# STM32.net
KiCad netlist of a schematic drawn in Altium Designer
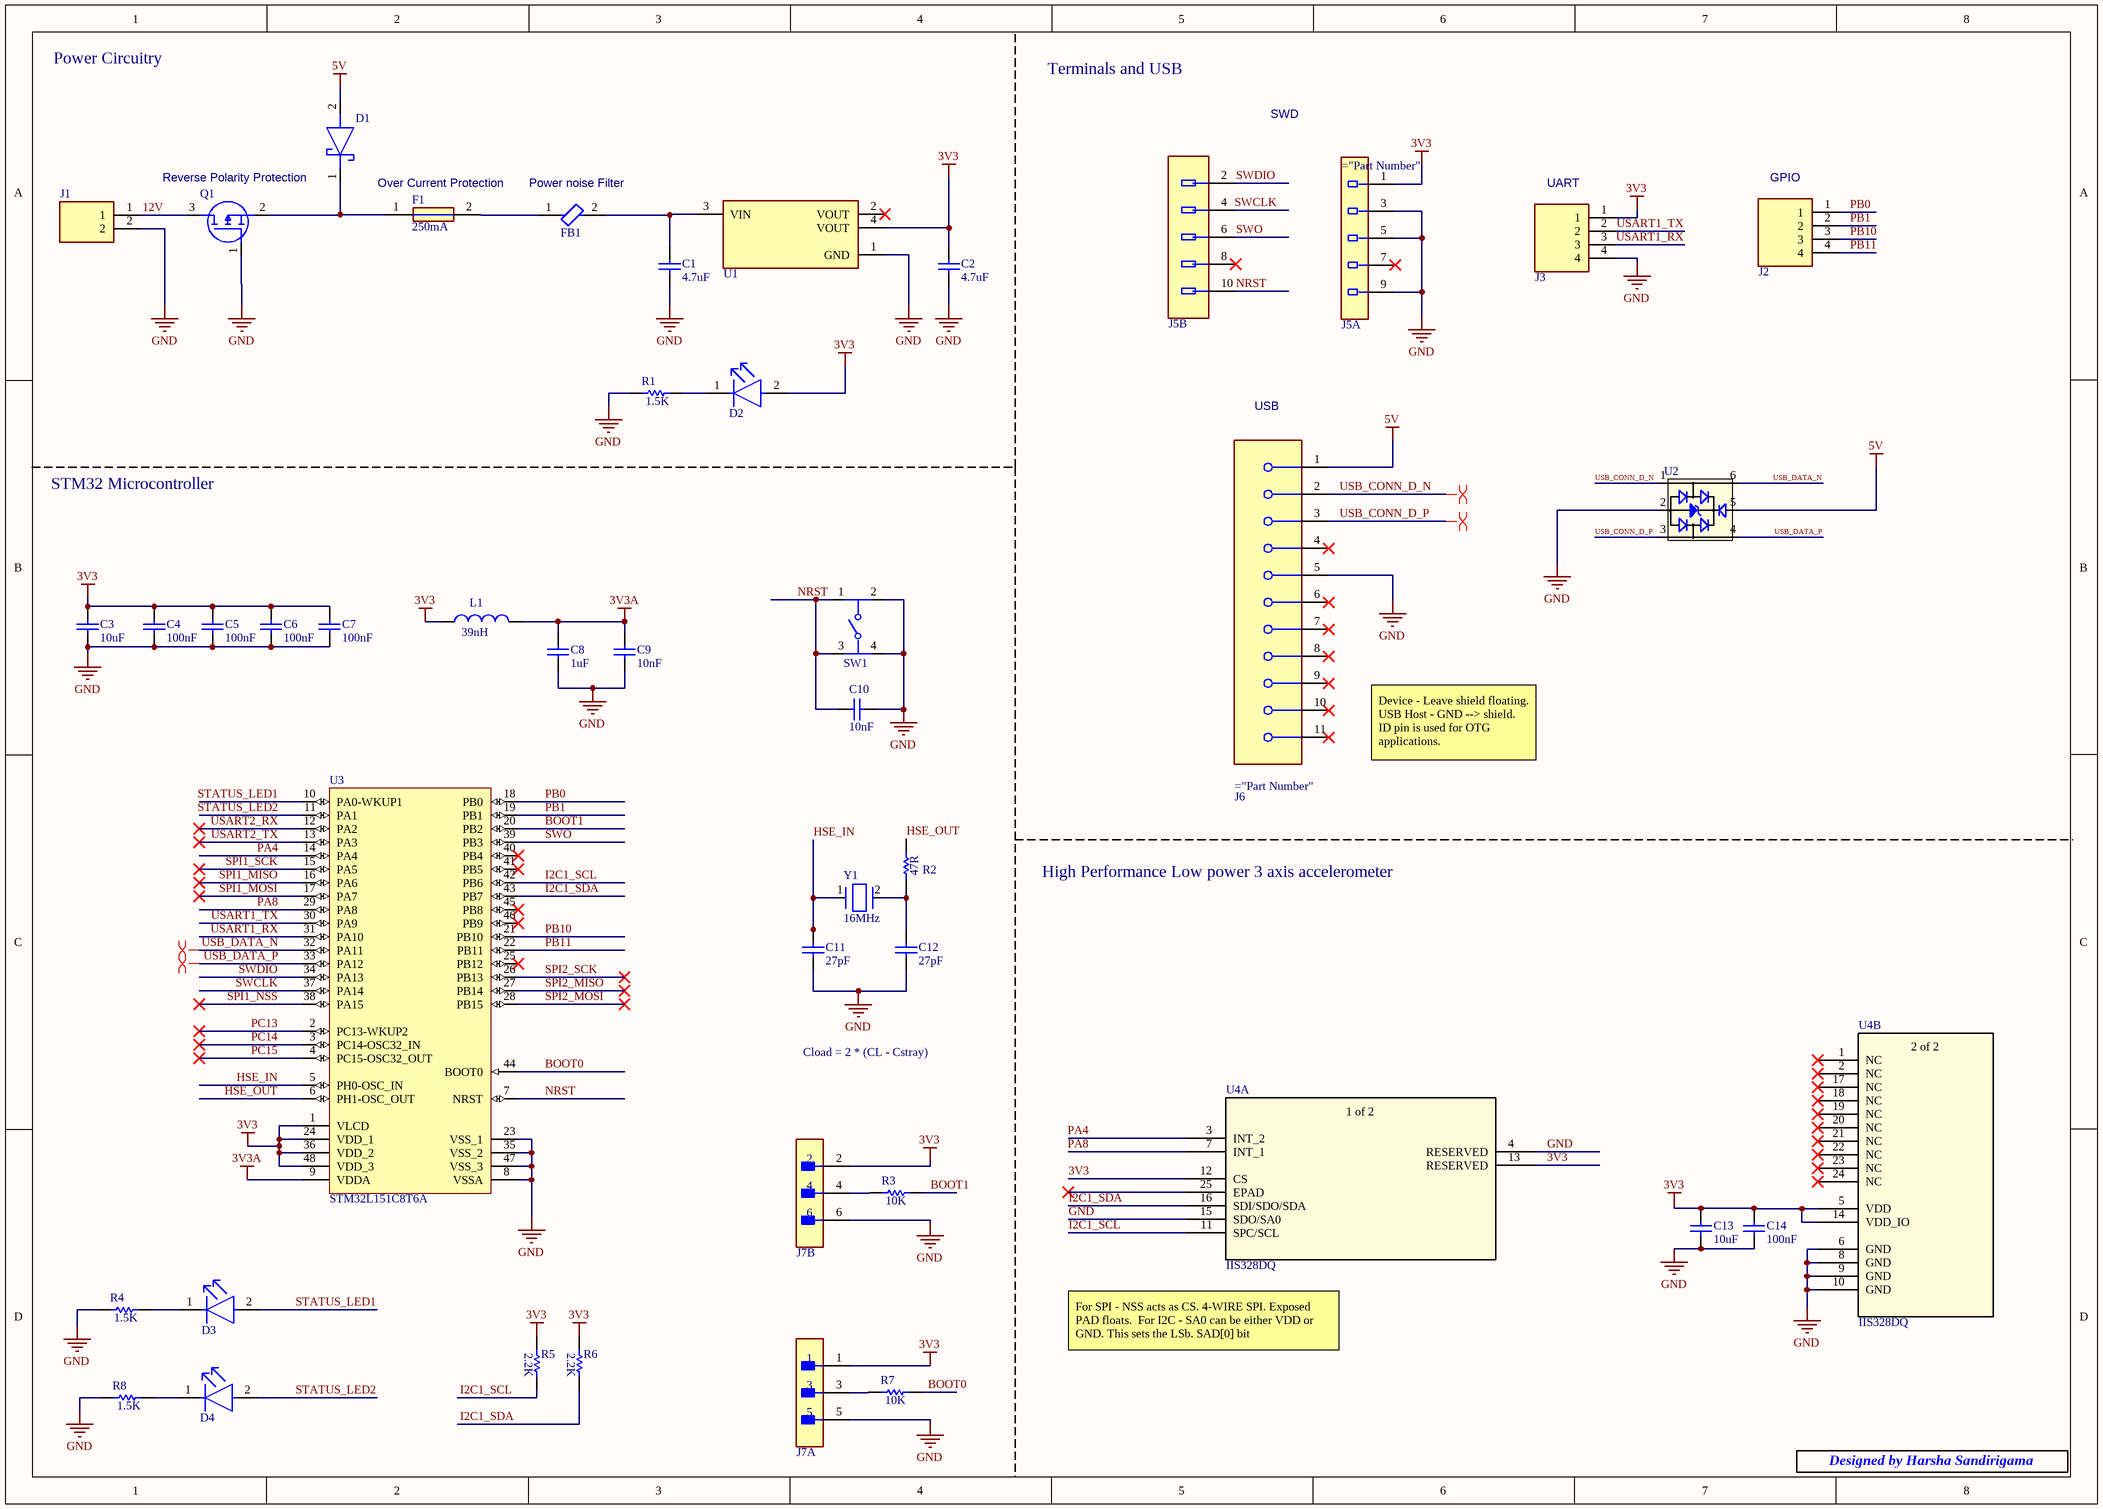
[diagram p0: STM32.SchDoc]

(export (version "E")
  (design (tool "Eeschema 10.0.6"))
  (components
    (comp (ref "C1")
      (value "4.7uF")
      (footprint "0603C - HD")
      (description "Cap Ceramic 4.7uF 10V X7S 10% SMD 0603 125°C Punched Paper T/R")
      (fields
        (field (name "MANUFACTURER") "TDK")
        (field (name "MANUFACTURER PART NUMBER") "C1608X7S1A475K080AC")
      )
      (libsource (lib "stm32devsch") (part "C1608X7S1A475K080AC"))
    )
    (comp (ref "C2")
      (value "4.7uF")
      (footprint "0603C - HD")
      (description "Cap Ceramic 4.7uF 10V X7S 10% SMD 0603 125°C Punched Paper T/R")
      (fields
        (field (name "MANUFACTURER") "TDK")
        (field (name "MANUFACTURER PART NUMBER") "C1608X7S1A475K080AC")
      )
      (libsource (lib "stm32devsch") (part "C1608X7S1A475K080AC"))
    )
    (comp (ref "C3")
      (value "10uF")
      (footprint "0603C - HD")
      (fields
        (field (name "MANUFACTURER") "Kyocera AVX")
        (field (name "MANUFACTURER PART NUMBER") "06036D106MAT2A")
        (field (name "TOLERANCE") "20%")
      )
      (libsource (lib "stm32devsch") (part "06036D106MAT2A"))
    )
    (comp (ref "C4")
      (value "100nF")
      (footprint "0603C - HD")
      (description "0.1 µF ±10% 50V Ceramic Capacitor X7R 0603 (1608 Metric)")
      (fields
        (field (name "MANUFACTURER") "Samsung")
        (field (name "MANUFACTURER PART NUMBER") "CL10B104KB8VPJC")
      )
      (libsource (lib "stm32devsch") (part "CL10B104KB8VPJC"))
    )
    (comp (ref "C5")
      (value "100nF")
      (footprint "0603C - HD")
      (description "0.1 µF ±10% 50V Ceramic Capacitor X7R 0603 (1608 Metric)")
      (fields
        (field (name "MANUFACTURER") "Samsung")
        (field (name "MANUFACTURER PART NUMBER") "CL10B104KB8VPJC")
      )
      (libsource (lib "stm32devsch") (part "CL10B104KB8VPJC"))
    )
    (comp (ref "C6")
      (value "100nF")
      (footprint "0603C - HD")
      (description "0.1 µF ±10% 50V Ceramic Capacitor X7R 0603 (1608 Metric)")
      (fields
        (field (name "MANUFACTURER") "Samsung")
        (field (name "MANUFACTURER PART NUMBER") "CL10B104KB8VPJC")
      )
      (libsource (lib "stm32devsch") (part "CL10B104KB8VPJC"))
    )
    (comp (ref "C7")
      (value "100nF")
      (footprint "0603C - HD")
      (description "0.1 µF ±10% 50V Ceramic Capacitor X7R 0603 (1608 Metric)")
      (fields
        (field (name "MANUFACTURER") "Samsung")
        (field (name "MANUFACTURER PART NUMBER") "CL10B104KB8VPJC")
      )
      (libsource (lib "stm32devsch") (part "CL10B104KB8VPJC"))
    )
    (comp (ref "C8")
      (value "1uF")
      (footprint "0603C - HD")
      (description "CAP CER 1UF 16V X7R 0603")
      (fields
        (field (name "MANUFACTURER") "Knowles Novacap")
        (field (name "MANUFACTURER PART NUMBER") "0603BB105K160YT")
      )
      (libsource (lib "stm32devsch") (part "0603BB105K160YT"))
    )
    (comp (ref "C9")
      (value "10nF")
      (footprint "0603C - HD")
      (description "Capacitor Ceramic 0.01uF 10% 50V 2-Pin Surface Mount T/R")
      (fields
        (field (name "MANUFACTURER") "Samsung")
        (field (name "MANUFACTURER PART NUMBER") "CL10B103KB8WPJC")
      )
      (libsource (lib "stm32devsch") (part "CL10B103KB8WPJC"))
    )
    (comp (ref "C10")
      (value "10nF")
      (footprint "0603C - HD")
      (description "Capacitor Ceramic 0.01uF 10% 50V 2-Pin Surface Mount T/R")
      (fields
        (field (name "MANUFACTURER") "Samsung")
        (field (name "MANUFACTURER PART NUMBER") "CL10B103KB8WPJC")
      )
      (libsource (lib "stm32devsch") (part "CL10B103KB8WPJC"))
    )
    (comp (ref "C11")
      (value "27pF")
      (footprint "0603C - HD")
      (description "CAP MLCC, 27PF, 50V, C0G/NP0, 5%, 0603")
      (fields
        (field (name "MANUFACTURER") "Kyocera AVX")
        (field (name "MANUFACTURER PART NUMBER") "06035A270JAT2A")
      )
      (libsource (lib "stm32devsch") (part "06035A270JAT2A"))
    )
    (comp (ref "C12")
      (value "27pF")
      (footprint "0603C - HD")
      (description "CAP MLCC, 27PF, 50V, C0G/NP0, 5%, 0603")
      (fields
        (field (name "MANUFACTURER") "Kyocera AVX")
        (field (name "MANUFACTURER PART NUMBER") "06035A270JAT2A")
      )
      (libsource (lib "stm32devsch") (part "06035A270JAT2A"))
    )
    (comp (ref "C13")
      (value "10uF")
      (footprint "0603C - HD")
      (fields
        (field (name "MANUFACTURER") "Kyocera AVX")
        (field (name "MANUFACTURER PART NUMBER") "06036D106MAT2A")
        (field (name "TOLERANCE") "20%")
      )
      (libsource (lib "stm32devsch") (part "06036D106MAT2A"))
    )
    (comp (ref "C14")
      (value "100nF")
      (footprint "0603C - HD")
      (description "0.1 µF ±10% 50V Ceramic Capacitor X7R 0603 (1608 Metric)")
      (fields
        (field (name "MANUFACTURER") "Samsung")
        (field (name "MANUFACTURER PART NUMBER") "CL10B104KB8VPJC")
      )
      (libsource (lib "stm32devsch") (part "CL10B104KB8VPJC"))
    )
    (comp (ref "D1")
      (value "PMEG4005CEJX")
      (footprint "SODFL2512X80N")
      (description "Rectifier Diode Schottky 40V 0.5A 1.8ns Automotive 2-Pin SOD-323F T/R")
      (fields (field (name "MOUSER PART NUMBER") "771-PMEG4005CEJX") (field (name "MANUFACTURER") "Nexperia"))
      (libsource (lib "stm32devsch") (part "PMEG4005CEJX"))
    )
    (comp (ref "D2")
      (value "LTST-C191KFKT")
      (footprint "Lite-On_0_MFG")
      (description "Orange 0603 130° Water Clear 90 mcd 2 V SMT Rectangular Flat Top LED")
      (fields (field (name "MANUFACTURER") "Vishay Lite-On"))
      (libsource (lib "stm32devsch") (part "LTST-C191KFKT"))
    )
    (comp (ref "D3")
      (value "LTST-C191KFKT")
      (footprint "Lite-On_0_MFG")
      (description "Orange 0603 130° Water Clear 90 mcd 2 V SMT Rectangular Flat Top LED")
      (fields (field (name "MANUFACTURER") "Vishay Lite-On"))
      (libsource (lib "stm32devsch") (part "LTST-C191KFKT"))
    )
    (comp (ref "D4")
      (value "LTST-C191KFKT")
      (footprint "Lite-On_0_MFG")
      (description "Orange 0603 130° Water Clear 90 mcd 2 V SMT Rectangular Flat Top LED")
      (fields (field (name "MANUFACTURER") "Vishay Lite-On"))
      (libsource (lib "stm32devsch") (part "LTST-C191KFKT"))
    )
    (comp (ref "F1")
      (value "250mA")
      (footprint "FUSC3115X66N")
      (description "Fuse Chip Very Fast Acting 0.25A 125V SMD Solder Pad 1206 Ceramic T/R CE/CSA/cULus")
      (fields (field (name "MANUFACTURER_PART_NUMBER") "C1Q250") (field (name "MANUFACTURER") "Bel"))
      (libsource (lib "stm32devsch") (part "C1Q250"))
    )
    (comp (ref "FB1")
      (value "MPZ1608Y101BTA00")
      (footprint "TDK_MPZ1608-0_8_IPC_A")
      (description "Ind Chip Bead Multi-Layer 100Ohm 25% 100MHz Ferrite 2A 0603 Punched Paper T/R")
      (fields (field (name "MANUFACTURER") "TDK") (field (name "TOLERANCE") "25%"))
      (libsource (lib "stm32devsch") (part "MPZ1608Y101BTA00"))
    )
    (comp (ref "J1")
      (value "12V")
      (footprint "PJ037AH")
      (description "CONN PWR JACK 2X5.5MM SOLDER")
      (fields
        (field (name "MANUFACTURER_PART_NUMBER") "PJ-037AH")
        (field (name "MOUSER PART NUMBER") "490-PJ-037AH")
      )
      (libsource (lib "stm32devsch") (part "PJ-037AH"))
    )
    (comp (ref "J2")
      (value "TS-104-T-AA")
      (footprint "HDRV4W46P0X254_1X4_1016X254X808P")
      (description "Connector")
      (fields (field (name "MOUSER PART NUMBER") "200-TS104TAA"))
      (libsource (lib "stm32devsch") (part "TS-104-T-AA"))
    )
    (comp (ref "J3")
      (value "TS-104-T-AA")
      (footprint "HDRV4W46P0X254_1X4_1016X254X808P")
      (description "Connector")
      (fields (field (name "MOUSER PART NUMBER") "200-TS104TAA"))
      (libsource (lib "stm32devsch") (part "TS-104-T-AA"))
    )
    (comp (ref "J5")
      (value "GRPB052VWQS-RC")
      (footprint "Sullins_GRPB052VWQS-RC_MFG")
      (description "Male, 10 C, SMT, .050\" CC; 3.00mm Head/5.10mm Tail, Sf Mt; No GP, Nylon 9T, Brass, 105 C")
      (fields (field (name "MANUFACTURER") "Sullins"))
      (libsource (lib "stm32devsch") (part "GRPB052VWQS-RC"))
    )
    (comp (ref "J6")
      (value "USB3075-30-A")
      (footprint "Global_Connector_Technology_USB3075-30-A_0")
      (description "Conn Micro USB Type B RCP 2Power/3Signal POS 0.65mm Solder RA SMD 5 Terminal 1 Port T/R")
      (fields (field (name "MANUFACTURER") "Global Connector Technology"))
      (libsource (lib "stm32devsch") (part "USB3075-30-A"))
    )
    (comp (ref "J7")
      (value "67996-406HLF")
      (footprint "Amphenol_ICC_-_FCI_0_MFG")
      (description "CONN HEADER VERT 6POS 2.54MM")
      (fields (field (name "MANUFACTURER") "Amphenol ICC / FCI"))
      (libsource (lib "stm32devsch") (part "67996-406HLF"))
    )
    (comp (ref "L1")
      (value "39nH")
      (footprint "0603L - HD")
      (description "Ind High Frequency Chip Multi-Layer 39nH 5% 100MHz 12Q-Factor Ceramic 300mA 0603 T/R")
      (fields
        (field (name "MANUFACTURER") "Taiyo Yuden")
        (field (name "MANUFACTURER PART NUMBER") "HK160839NJ-T")
      )
      (libsource (lib "stm32devsch") (part "HK160839NJ-T"))
    )
    (comp (ref "Q1")
      (value "MOSFET P-CH")
      (footprint "SOT96P240X110-3N")
      (description "Trans MOSFET P-CH 30V 3.5A Automotive 3-Pin SOT-23 T/R")
      (fields
        (field (name "MANUFACTURER_PART_NUMBER") "DMP3130LQ-7")
        (field (name "MOUSER PART NUMBER") "621-DMP3130LQ-7")
      )
      (libsource (lib "stm32devsch") (part "DMP3130LQ-7"))
    )
    (comp (ref "R1")
      (value "RMCF0603FT1K50")
      (footprint "0603R - HD")
      (description "Res Thick Film 0603 1.5K Ohm 1% 0.1W(1/10W) ±100ppm/C Pad SMD Automotive T/R")
      (fields (field (name "MANUFACTURER") "Stackpole Electronics") (field (name "TOLERANCE") "1%"))
      (libsource (lib "stm32devsch") (part "RMCF0603FT1K50"))
    )
    (comp (ref "R2")
      (value "47R")
      (footprint "0603R - HD")
      (description "RES SMD 47 OHM 1% 1/4W 0603")
      (fields
        (field (name "MANUFACTURER") "Vishay Dale")
        (field (name "MANUFACTURER PART NUMBER") "RCS060347R0FKEA")
      )
      (libsource (lib "stm32devsch") (part "RCS060347R0FKEA"))
    )
    (comp (ref "R3")
      (value "RNCF0603BTE10K0")
      (footprint "0603R - HD")
      (description "RES 10K OHM 0.1% 1/10W 0603")
      (libsource (lib "stm32devsch") (part "RNCF0603BTE10K0"))
    )
    (comp (ref "R4")
      (value "RMCF0603FT1K50")
      (footprint "0603R - HD")
      (description "Res Thick Film 0603 1.5K Ohm 1% 0.1W(1/10W) ±100ppm/C Pad SMD Automotive T/R")
      (fields (field (name "MANUFACTURER") "Stackpole Electronics") (field (name "TOLERANCE") "1%"))
      (libsource (lib "stm32devsch") (part "RMCF0603FT1K50"))
    )
    (comp (ref "R5")
      (value "RMCF0603FT2K20")
      (footprint "0603R - HD")
      (description "Res Thick Film 0603 2.2K Ohm 1% 0.1W(1/10W) ±100ppm/C Pad SMD Automotive T/R")
      (fields (field (name "MANUFACTURER") "Stackpole Electronics") (field (name "TOLERANCE") "1%"))
      (libsource (lib "stm32devsch") (part "RMCF0603FT2K20"))
    )
    (comp (ref "R6")
      (value "RMCF0603FT2K20")
      (footprint "0603R - HD")
      (description "Res Thick Film 0603 2.2K Ohm 1% 0.1W(1/10W) ±100ppm/C Pad SMD Automotive T/R")
      (fields (field (name "MANUFACTURER") "Stackpole Electronics") (field (name "TOLERANCE") "1%"))
      (libsource (lib "stm32devsch") (part "RMCF0603FT2K20"))
    )
    (comp (ref "R7")
      (value "RNCF0603BTE10K0")
      (footprint "0603R - HD")
      (description "RES 10K OHM 0.1% 1/10W 0603")
      (libsource (lib "stm32devsch") (part "RNCF0603BTE10K0"))
    )
    (comp (ref "R8")
      (value "RMCF0603FT1K50")
      (footprint "0603R - HD")
      (description "Res Thick Film 0603 1.5K Ohm 1% 0.1W(1/10W) ±100ppm/C Pad SMD Automotive T/R")
      (fields (field (name "MANUFACTURER") "Stackpole Electronics") (field (name "TOLERANCE") "1%"))
      (libsource (lib "stm32devsch") (part "RMCF0603FT1K50"))
    )
    (comp (ref "SW1")
      (value "PTS645SM43SMTR92LFS")
      (footprint "C&K_0_MFG - duplicate")
      (description "SWITCH TACTILE SPST-NO 0.05A 12V")
      (fields (field (name "MANUFACTURER") "ITT C&K"))
      (libsource (lib "stm32devsch") (part "PTS645SM43SMTR92LFS"))
    )
    (comp (ref "U1")
      (value "ZLDO1117G33TA")
      (footprint "Diodes_SOT223_IPC_A")
      (description "LDO Regulator Pos 3.3V 1A 4-Pin(3+Tab) SOT-223 T/R / IC REG LDO 3.3V 1A SOT223")
      (fields (field (name "MANUFACTURER") "Diodes Zetex") (field (name "TOLERANCE") "2%"))
      (libsource (lib "stm32devsch") (part "ZLDO1117G33TA"))
    )
    (comp (ref "U2")
      (value "82400102")
      (footprint "SOT23_6L")
      (description "TVS Diode Array WE-TVS 2-Ch+VDD 5V SOT23")
      (fields (field (name "MANUFACTURER") "Wuerth Elektronik"))
      (libsource (lib "stm32devsch") (part "CMP-1486-00007-1"))
    )
    (comp (ref "U3")
      (value "STM32L151C8T6A")
      (footprint "QFP50P900X900X160-48N")
      (description "MCU 32-bit ARM Cortex M3 RISC 64KB Flash 2.5V/3.3V 48-Pin LQFP Tray")
      (fields (field (name "MANUFACTURER") "STMicroelectronics"))
      (libsource (lib "stm32devsch") (part "STM32L151C8T6A_1"))
    )
    (comp (ref "U4")
      (value "IIS328DQ")
      (footprint "QFN-24_4X4MM_STM")
      (description "High Performance Low power 3 axis accelerometer for industrial applications")
      (fields
        (field (name "MANUFACTURER") "STMicroelectronics")
        (field (name "MANUFACTURER PART NUMBER") "IIS328DQTR")
        (field (name "COPYRIGHT") "Copyright (C) 2021 Ultra Librarian. All rights reserved.")
      )
      (libsource (lib "stm32devsch") (part "IIS328DQ"))
    )
    (comp (ref "Y1")
      (value "16MHz")
      (footprint "ECS_Inc._ECS-160-20-3X-TR_0")
      (description "Crystals 16MHz 20pF 50ppm -10C +70C")
      (fields (field (name "PART NUMBER") "ECS-160-20-3X-TR") (field (name "MANUFACTURER") "ECS Inc."))
      (libsource (lib "stm32devsch") (part "Crys_ECS_Inc._ECS-160-20-3X-TR_eec"))
    )
  )
  (nets
    (net (code "1") (name "/12V") (class "Default")
      (node (ref "J1") (pin "1") (pinfunction "1_1") (pintype "passive"))
      (node (ref "Q1") (pin "3") (pinfunction "D_3") (pintype "passive"))
    )
    (net (code "2") (name "/BOOT0") (class "Default")
      (node (ref "R7") (pin "2") (pinfunction "2_2") (pintype "passive"))
      (node (ref "U3") (pin "44") (pinfunction "BOOT0_44") (pintype "input"))
    )
    (net (code "3") (name "/BOOT1") (class "Default")
      (node (ref "R3") (pin "2") (pinfunction "2_2") (pintype "passive"))
      (node (ref "U3") (pin "20") (pinfunction "PB2_20") (pintype "bidirectional"))
    )
    (net (code "4") (name "/HSE_IN") (class "Default")
      (node (ref "C11") (pin "2") (pinfunction "2_2") (pintype "passive"))
      (node (ref "U3") (pin "5") (pinfunction "PH0-OSC_IN_5") (pintype "bidirectional"))
      (node (ref "Y1") (pin "1") (pinfunction "1_1") (pintype "passive"))
    )
    (net (code "5") (name "/HSE_OUT") (class "Default")
      (node (ref "R2") (pin "2") (pinfunction "2_2") (pintype "passive"))
      (node (ref "U3") (pin "6") (pinfunction "PH1-OSC_OUT_6") (pintype "bidirectional"))
    )
    (net (code "6") (name "/I2C1_SCL") (class "Default")
      (node (ref "R5") (pin "2") (pinfunction "2_2") (pintype "passive"))
      (node (ref "U3") (pin "42") (pinfunction "PB6_42") (pintype "bidirectional"))
      (node (ref "U4") (pin "11") (pinfunction "SPC/SCL_11") (pintype "passive"))
    )
    (net (code "7") (name "/I2C1_SDA") (class "Default")
      (node (ref "R6") (pin "2") (pinfunction "2_2") (pintype "passive"))
      (node (ref "U3") (pin "43") (pinfunction "PB7_43") (pintype "bidirectional"))
      (node (ref "U4") (pin "16") (pinfunction "SDI/SDO/SDA_16") (pintype "passive"))
    )
    (net (code "8") (name "/NRST") (class "Default")
      (node (ref "C10") (pin "1") (pinfunction "1_1") (pintype "passive"))
      (node (ref "J5") (pin "10") (pinfunction "10_10") (pintype "passive"))
      (node (ref "SW1") (pin "1") (pinfunction "1_1") (pintype "passive"))
      (node (ref "SW1") (pin "3") (pinfunction "3_3") (pintype "passive"))
      (node (ref "U3") (pin "7") (pinfunction "NRST_7") (pintype "bidirectional"))
    )
    (net (code "9") (name "/PA4") (class "Default")
      (node (ref "U3") (pin "14") (pinfunction "PA4_14") (pintype "bidirectional"))
      (node (ref "U4") (pin "3") (pinfunction "INT_2_3") (pintype "passive"))
    )
    (net (code "10") (name "/PA8") (class "Default")
      (node (ref "U3") (pin "29") (pinfunction "PA8_29") (pintype "bidirectional"))
      (node (ref "U4") (pin "7") (pinfunction "INT_1_7") (pintype "passive"))
    )
    (net (code "11") (name "/PB0") (class "Default")
      (node (ref "J2") (pin "1") (pinfunction "1_1") (pintype "passive"))
      (node (ref "U3") (pin "18") (pinfunction "PB0_18") (pintype "bidirectional"))
    )
    (net (code "12") (name "/PB1") (class "Default")
      (node (ref "J2") (pin "2") (pinfunction "2_2") (pintype "passive"))
      (node (ref "U3") (pin "19") (pinfunction "PB1_19") (pintype "bidirectional"))
    )
    (net (code "13") (name "/PB10") (class "Default")
      (node (ref "J2") (pin "3") (pinfunction "3_3") (pintype "passive"))
      (node (ref "U3") (pin "21") (pinfunction "PB10_21") (pintype "bidirectional"))
    )
    (net (code "14") (name "/PB11") (class "Default")
      (node (ref "J2") (pin "4") (pinfunction "4_4") (pintype "passive"))
      (node (ref "U3") (pin "22") (pinfunction "PB11_22") (pintype "bidirectional"))
    )
    (net (code "15") (name "/PC13") (class "Default")
      (node (ref "U3") (pin "2") (pinfunction "PC13-WKUP2_2") (pintype "bidirectional+no_connect"))
    )
    (net (code "16") (name "/PC14") (class "Default")
      (node (ref "U3") (pin "3") (pinfunction "PC14-OSC32_IN_3") (pintype "bidirectional+no_connect"))
    )
    (net (code "17") (name "/PC15") (class "Default")
      (node (ref "U3") (pin "4") (pinfunction "PC15-OSC32_OUT_4") (pintype "bidirectional+no_connect"))
    )
    (net (code "18") (name "/SPI1_MISO") (class "Default")
      (node (ref "U3") (pin "16") (pinfunction "PA6_16") (pintype "bidirectional+no_connect"))
    )
    (net (code "19") (name "/SPI1_MOSI") (class "Default")
      (node (ref "U3") (pin "17") (pinfunction "PA7_17") (pintype "bidirectional+no_connect"))
    )
    (net (code "20") (name "/SPI1_NSS") (class "Default")
      (node (ref "U3") (pin "38") (pinfunction "PA15_38") (pintype "bidirectional+no_connect"))
    )
    (net (code "21") (name "/SPI1_SCK") (class "Default")
      (node (ref "U3") (pin "15") (pinfunction "PA5_15") (pintype "bidirectional+no_connect"))
    )
    (net (code "22") (name "/SPI2_MISO") (class "Default")
      (node (ref "U3") (pin "27") (pinfunction "PB14_27") (pintype "bidirectional+no_connect"))
    )
    (net (code "23") (name "/SPI2_MOSI") (class "Default")
      (node (ref "U3") (pin "28") (pinfunction "PB15_28") (pintype "bidirectional+no_connect"))
    )
    (net (code "24") (name "/SPI2_SCK") (class "Default")
      (node (ref "U3") (pin "26") (pinfunction "PB13_26") (pintype "bidirectional+no_connect"))
    )
    (net (code "25") (name "/STATUS_LED1") (class "Default")
      (node (ref "D3") (pin "2") (pinfunction "A_2") (pintype "passive"))
      (node (ref "U3") (pin "10") (pinfunction "PA0-WKUP1_10") (pintype "bidirectional"))
    )
    (net (code "26") (name "/STATUS_LED2") (class "Default")
      (node (ref "D4") (pin "2") (pinfunction "A_2") (pintype "passive"))
      (node (ref "U3") (pin "11") (pinfunction "PA1_11") (pintype "bidirectional"))
    )
    (net (code "27") (name "/SWCLK") (class "Default")
      (node (ref "J5") (pin "4") (pinfunction "4_4") (pintype "passive"))
      (node (ref "U3") (pin "37") (pinfunction "PA14_37") (pintype "bidirectional"))
    )
    (net (code "28") (name "/SWDIO") (class "Default")
      (node (ref "J5") (pin "2") (pinfunction "2_2") (pintype "passive"))
      (node (ref "U3") (pin "34") (pinfunction "PA13_34") (pintype "bidirectional"))
    )
    (net (code "29") (name "/SWO") (class "Default")
      (node (ref "J5") (pin "6") (pinfunction "6_6") (pintype "passive"))
      (node (ref "U3") (pin "39") (pinfunction "PB3_39") (pintype "bidirectional"))
    )
    (net (code "30") (name "/USART1_RX") (class "Default")
      (node (ref "J3") (pin "3") (pinfunction "3_3") (pintype "passive"))
      (node (ref "U3") (pin "31") (pinfunction "PA10_31") (pintype "bidirectional"))
    )
    (net (code "31") (name "/USART1_TX") (class "Default")
      (node (ref "J3") (pin "2") (pinfunction "2_2") (pintype "passive"))
      (node (ref "U3") (pin "30") (pinfunction "PA9_30") (pintype "bidirectional"))
    )
    (net (code "32") (name "/USART2_RX") (class "Default")
      (node (ref "U3") (pin "12") (pinfunction "PA2_12") (pintype "bidirectional+no_connect"))
    )
    (net (code "33") (name "/USART2_TX") (class "Default")
      (node (ref "U3") (pin "13") (pinfunction "PA3_13") (pintype "bidirectional+no_connect"))
    )
    (net (code "34") (name "/USB_CONN_D_N") (class "Default")
      (node (ref "J6") (pin "2") (pinfunction "2_2") (pintype "passive"))
      (node (ref "U2") (pin "1") (pinfunction "I/O1_1") (pintype "passive"))
    )
    (net (code "35") (name "/USB_CONN_D_P") (class "Default")
      (node (ref "J6") (pin "3") (pinfunction "3_3") (pintype "passive"))
      (node (ref "U2") (pin "3") (pinfunction "I/O2_3") (pintype "passive"))
    )
    (net (code "36") (name "/USB_DATA_N") (class "Default")
      (node (ref "U2") (pin "6") (pinfunction "I/O1_6") (pintype "passive"))
      (node (ref "U3") (pin "32") (pinfunction "PA11_32") (pintype "bidirectional"))
    )
    (net (code "37") (name "/USB_DATA_P") (class "Default")
      (node (ref "U2") (pin "4") (pinfunction "I/O2_4") (pintype "passive"))
      (node (ref "U3") (pin "33") (pinfunction "PA12_33") (pintype "bidirectional"))
    )
    (net (code "38") (name "3V3") (class "Default")
      (node (ref "C13") (pin "2") (pinfunction "2_2") (pintype "passive"))
      (node (ref "C14") (pin "2") (pinfunction "2_2") (pintype "passive"))
      (node (ref "C2") (pin "2") (pinfunction "2_2") (pintype "passive"))
      (node (ref "C3") (pin "2") (pinfunction "2_2") (pintype "passive"))
      (node (ref "C4") (pin "2") (pinfunction "2_2") (pintype "passive"))
      (node (ref "C5") (pin "2") (pinfunction "2_2") (pintype "passive"))
      (node (ref "C6") (pin "2") (pinfunction "2_2") (pintype "passive"))
      (node (ref "C7") (pin "2") (pinfunction "2_2") (pintype "passive"))
      (node (ref "D2") (pin "2") (pinfunction "A_2") (pintype "passive"))
      (node (ref "J3") (pin "1") (pinfunction "1_1") (pintype "passive"))
      (node (ref "J5") (pin "1") (pinfunction "1_1") (pintype "passive"))
      (node (ref "J7") (pin "1") (pinfunction "1_1") (pintype "passive"))
      (node (ref "J7") (pin "2") (pinfunction "2_2") (pintype "passive"))
      (node (ref "L1") (pin "1") (pinfunction "1_1") (pintype "passive"))
      (node (ref "R5") (pin "1") (pinfunction "1_1") (pintype "passive"))
      (node (ref "R6") (pin "1") (pinfunction "1_1") (pintype "passive"))
      (node (ref "U1") (pin "4") (pinfunction "VOUT_4") (pintype "power_in"))
      (node (ref "U3") (pin "1") (pinfunction "VLCD_1") (pintype "power_in"))
      (node (ref "U3") (pin "24") (pinfunction "VDD_1_24") (pintype "power_in"))
      (node (ref "U3") (pin "36") (pinfunction "VDD_2_36") (pintype "power_in"))
      (node (ref "U3") (pin "48") (pinfunction "VDD_3_48") (pintype "power_in"))
      (node (ref "U4") (pin "12") (pinfunction "CS_12") (pintype "passive"))
      (node (ref "U4") (pin "13") (pinfunction "RESERVED_13") (pintype "passive"))
      (node (ref "U4") (pin "14") (pinfunction "VDD_IO_14") (pintype "power_in"))
      (node (ref "U4") (pin "5") (pinfunction "VDD_5") (pintype "power_in"))
    )
    (net (code "39") (name "3V3A") (class "Default")
      (node (ref "C8") (pin "2") (pinfunction "2_2") (pintype "passive"))
      (node (ref "C9") (pin "2") (pinfunction "2_2") (pintype "passive"))
      (node (ref "L1") (pin "2") (pinfunction "2_2") (pintype "passive"))
      (node (ref "U3") (pin "9") (pinfunction "VDDA_9") (pintype "power_in"))
    )
    (net (code "40") (name "5V") (class "Default")
      (node (ref "D1") (pin "2") (pinfunction "A_2") (pintype "passive"))
      (node (ref "J6") (pin "1") (pinfunction "1_1") (pintype "passive"))
      (node (ref "U2") (pin "5") (pinfunction "VDD_5") (pintype "passive"))
    )
    (net (code "41") (name "GND") (class "Default")
      (node (ref "C1") (pin "1") (pinfunction "1_1") (pintype "passive"))
      (node (ref "C10") (pin "2") (pinfunction "2_2") (pintype "passive"))
      (node (ref "C11") (pin "1") (pinfunction "1_1") (pintype "passive"))
      (node (ref "C12") (pin "1") (pinfunction "1_1") (pintype "passive"))
      (node (ref "C13") (pin "1") (pinfunction "1_1") (pintype "passive"))
      (node (ref "C14") (pin "1") (pinfunction "1_1") (pintype "passive"))
      (node (ref "C2") (pin "1") (pinfunction "1_1") (pintype "passive"))
      (node (ref "C3") (pin "1") (pinfunction "1_1") (pintype "passive"))
      (node (ref "C4") (pin "1") (pinfunction "1_1") (pintype "passive"))
      (node (ref "C5") (pin "1") (pinfunction "1_1") (pintype "passive"))
      (node (ref "C6") (pin "1") (pinfunction "1_1") (pintype "passive"))
      (node (ref "C7") (pin "1") (pinfunction "1_1") (pintype "passive"))
      (node (ref "C8") (pin "1") (pinfunction "1_1") (pintype "passive"))
      (node (ref "C9") (pin "1") (pinfunction "1_1") (pintype "passive"))
      (node (ref "J1") (pin "2") (pinfunction "2_2") (pintype "passive"))
      (node (ref "J3") (pin "4") (pinfunction "4_4") (pintype "passive"))
      (node (ref "J5") (pin "3") (pinfunction "3_3") (pintype "passive"))
      (node (ref "J5") (pin "5") (pinfunction "5_5") (pintype "passive"))
      (node (ref "J5") (pin "9") (pinfunction "9_9") (pintype "passive"))
      (node (ref "J6") (pin "5") (pinfunction "5_5") (pintype "passive"))
      (node (ref "J7") (pin "5") (pinfunction "5_5") (pintype "passive"))
      (node (ref "J7") (pin "6") (pinfunction "6_6") (pintype "passive"))
      (node (ref "Q1") (pin "1") (pinfunction "G_1") (pintype "passive"))
      (node (ref "R1") (pin "1") (pinfunction "1_1") (pintype "passive"))
      (node (ref "R4") (pin "1") (pinfunction "1_1") (pintype "passive"))
      (node (ref "R8") (pin "1") (pinfunction "1_1") (pintype "passive"))
      (node (ref "SW1") (pin "2") (pinfunction "2_2") (pintype "passive"))
      (node (ref "SW1") (pin "4") (pinfunction "4_4") (pintype "passive"))
      (node (ref "U1") (pin "1") (pinfunction "GND_1") (pintype "power_in"))
      (node (ref "U2") (pin "2") (pinfunction "GND_2") (pintype "passive"))
      (node (ref "U3") (pin "23") (pinfunction "VSS_1_23") (pintype "power_in"))
      (node (ref "U3") (pin "35") (pinfunction "VSS_2_35") (pintype "power_in"))
      (node (ref "U3") (pin "47") (pinfunction "VSS_3_47") (pintype "power_in"))
      (node (ref "U3") (pin "8") (pinfunction "VSSA_8") (pintype "power_in"))
      (node (ref "U4") (pin "10") (pinfunction "GND_10") (pintype "power_in"))
      (node (ref "U4") (pin "15") (pinfunction "SDO/SA0_15") (pintype "passive"))
      (node (ref "U4") (pin "4") (pinfunction "RESERVED_4") (pintype "passive"))
      (node (ref "U4") (pin "6") (pinfunction "GND_6") (pintype "power_in"))
      (node (ref "U4") (pin "8") (pinfunction "GND_8") (pintype "power_in"))
      (node (ref "U4") (pin "9") (pinfunction "GND_9") (pintype "power_in"))
    )
    (net (code "42") (name "Net-(C12-Pad2)") (class "Default")
      (node (ref "C12") (pin "2") (pinfunction "2_2") (pintype "passive"))
      (node (ref "R2") (pin "1") (pinfunction "1_1") (pintype "passive"))
      (node (ref "Y1") (pin "2") (pinfunction "2_2") (pintype "passive"))
    )
    (net (code "43") (name "Net-(D1-K)") (class "Default")
      (node (ref "D1") (pin "1") (pinfunction "K_1") (pintype "passive"))
      (node (ref "F1") (pin "1") (pinfunction "1_1") (pintype "passive"))
      (node (ref "Q1") (pin "2") (pinfunction "S_2") (pintype "passive"))
    )
    (net (code "44") (name "Net-(D2-C)") (class "Default")
      (node (ref "D2") (pin "1") (pinfunction "C_1") (pintype "passive"))
      (node (ref "R1") (pin "2") (pinfunction "2_2") (pintype "passive"))
    )
    (net (code "45") (name "Net-(D3-C)") (class "Default")
      (node (ref "D3") (pin "1") (pinfunction "C_1") (pintype "passive"))
      (node (ref "R4") (pin "2") (pinfunction "2_2") (pintype "passive"))
    )
    (net (code "46") (name "Net-(D4-C)") (class "Default")
      (node (ref "D4") (pin "1") (pinfunction "C_1") (pintype "passive"))
      (node (ref "R8") (pin "2") (pinfunction "2_2") (pintype "passive"))
    )
    (net (code "47") (name "Net-(F1-Pad2)") (class "Default")
      (node (ref "F1") (pin "2") (pinfunction "2_2") (pintype "passive"))
      (node (ref "FB1") (pin "1") (pinfunction "1_1") (pintype "passive"))
    )
    (net (code "48") (name "Net-(J7-Pad3)") (class "Default")
      (node (ref "J7") (pin "3") (pinfunction "3_3") (pintype "passive"))
      (node (ref "R7") (pin "1") (pinfunction "1_1") (pintype "passive"))
    )
    (net (code "49") (name "Net-(J7-Pad4)") (class "Default")
      (node (ref "J7") (pin "4") (pinfunction "4_4") (pintype "passive"))
      (node (ref "R3") (pin "1") (pinfunction "1_1") (pintype "passive"))
    )
    (net (code "50") (name "Net-(U1-VIN)") (class "Default")
      (node (ref "C1") (pin "2") (pinfunction "2_2") (pintype "passive"))
      (node (ref "FB1") (pin "2") (pinfunction "2_2") (pintype "passive"))
      (node (ref "U1") (pin "3") (pinfunction "VIN_3") (pintype "power_in"))
    )
    (net (code "51") (name "unconnected-(J5-Pad7)") (class "Default")
      (node (ref "J5") (pin "7") (pinfunction "7_7") (pintype "passive+no_connect"))
    )
    (net (code "52") (name "unconnected-(J5-Pad8)") (class "Default")
      (node (ref "J5") (pin "8") (pinfunction "8_8") (pintype "passive+no_connect"))
    )
    (net (code "53") (name "unconnected-(J6-MNT_1-Pad6)") (class "Default")
      (node (ref "J6") (pin "6") (pinfunction "MNT_1_6") (pintype "passive+no_connect"))
    )
    (net (code "54") (name "unconnected-(J6-MNT_2-Pad7)") (class "Default")
      (node (ref "J6") (pin "7") (pinfunction "MNT_2_7") (pintype "passive+no_connect"))
    )
    (net (code "55") (name "unconnected-(J6-MNT_3-Pad8)") (class "Default")
      (node (ref "J6") (pin "8") (pinfunction "MNT_3_8") (pintype "passive+no_connect"))
    )
    (net (code "56") (name "unconnected-(J6-MNT_4-Pad9)") (class "Default")
      (node (ref "J6") (pin "9") (pinfunction "MNT_4_9") (pintype "passive+no_connect"))
    )
    (net (code "57") (name "unconnected-(J6-MNT_5-Pad10)") (class "Default")
      (node (ref "J6") (pin "10") (pinfunction "MNT_5_10") (pintype "passive+no_connect"))
    )
    (net (code "58") (name "unconnected-(J6-MNT_6-Pad11)") (class "Default")
      (node (ref "J6") (pin "11") (pinfunction "MNT_6_11") (pintype "passive+no_connect"))
    )
    (net (code "59") (name "unconnected-(J6-Pad4)") (class "Default")
      (node (ref "J6") (pin "4") (pinfunction "4_4") (pintype "passive+no_connect"))
    )
    (net (code "60") (name "unconnected-(U1-VOUT-Pad2)") (class "Default")
      (node (ref "U1") (pin "2") (pinfunction "VOUT_2") (pintype "power_in+no_connect"))
    )
    (net (code "61") (name "unconnected-(U3-PB4-Pad40)") (class "Default")
      (node (ref "U3") (pin "40") (pinfunction "PB4_40") (pintype "bidirectional+no_connect"))
    )
    (net (code "62") (name "unconnected-(U3-PB5-Pad41)") (class "Default")
      (node (ref "U3") (pin "41") (pinfunction "PB5_41") (pintype "bidirectional+no_connect"))
    )
    (net (code "63") (name "unconnected-(U3-PB8-Pad45)") (class "Default")
      (node (ref "U3") (pin "45") (pinfunction "PB8_45") (pintype "bidirectional+no_connect"))
    )
    (net (code "64") (name "unconnected-(U3-PB9-Pad46)") (class "Default")
      (node (ref "U3") (pin "46") (pinfunction "PB9_46") (pintype "bidirectional+no_connect"))
    )
    (net (code "65") (name "unconnected-(U3-PB12-Pad25)") (class "Default")
      (node (ref "U3") (pin "25") (pinfunction "PB12_25") (pintype "bidirectional+no_connect"))
    )
    (net (code "66") (name "unconnected-(U4A-EPAD-Pad25)") (class "Default")
      (node (ref "U4") (pin "25") (pinfunction "EPAD_25") (pintype "passive+no_connect"))
    )
    (net (code "67") (name "unconnected-(U4B-NC-Pad1)") (class "Default")
      (node (ref "U4") (pin "1") (pinfunction "NC_1") (pintype "passive+no_connect"))
    )
    (net (code "68") (name "unconnected-(U4B-NC-Pad2)") (class "Default")
      (node (ref "U4") (pin "2") (pinfunction "NC_2") (pintype "passive+no_connect"))
    )
    (net (code "69") (name "unconnected-(U4B-NC-Pad17)") (class "Default")
      (node (ref "U4") (pin "17") (pinfunction "NC_17") (pintype "passive+no_connect"))
    )
    (net (code "70") (name "unconnected-(U4B-NC-Pad18)") (class "Default")
      (node (ref "U4") (pin "18") (pinfunction "NC_18") (pintype "passive+no_connect"))
    )
    (net (code "71") (name "unconnected-(U4B-NC-Pad19)") (class "Default")
      (node (ref "U4") (pin "19") (pinfunction "NC_19") (pintype "passive+no_connect"))
    )
    (net (code "72") (name "unconnected-(U4B-NC-Pad20)") (class "Default")
      (node (ref "U4") (pin "20") (pinfunction "NC_20") (pintype "passive+no_connect"))
    )
    (net (code "73") (name "unconnected-(U4B-NC-Pad21)") (class "Default")
      (node (ref "U4") (pin "21") (pinfunction "NC_21") (pintype "passive+no_connect"))
    )
    (net (code "74") (name "unconnected-(U4B-NC-Pad22)") (class "Default")
      (node (ref "U4") (pin "22") (pinfunction "NC_22") (pintype "passive+no_connect"))
    )
    (net (code "75") (name "unconnected-(U4B-NC-Pad23)") (class "Default")
      (node (ref "U4") (pin "23") (pinfunction "NC_23") (pintype "passive+no_connect"))
    )
    (net (code "76") (name "unconnected-(U4B-NC-Pad24)") (class "Default")
      (node (ref "U4") (pin "24") (pinfunction "NC_24") (pintype "passive+no_connect"))
    )
  )
)
